# Buffer.net
KiCad netlist of a schematic drawn in Altium Designer
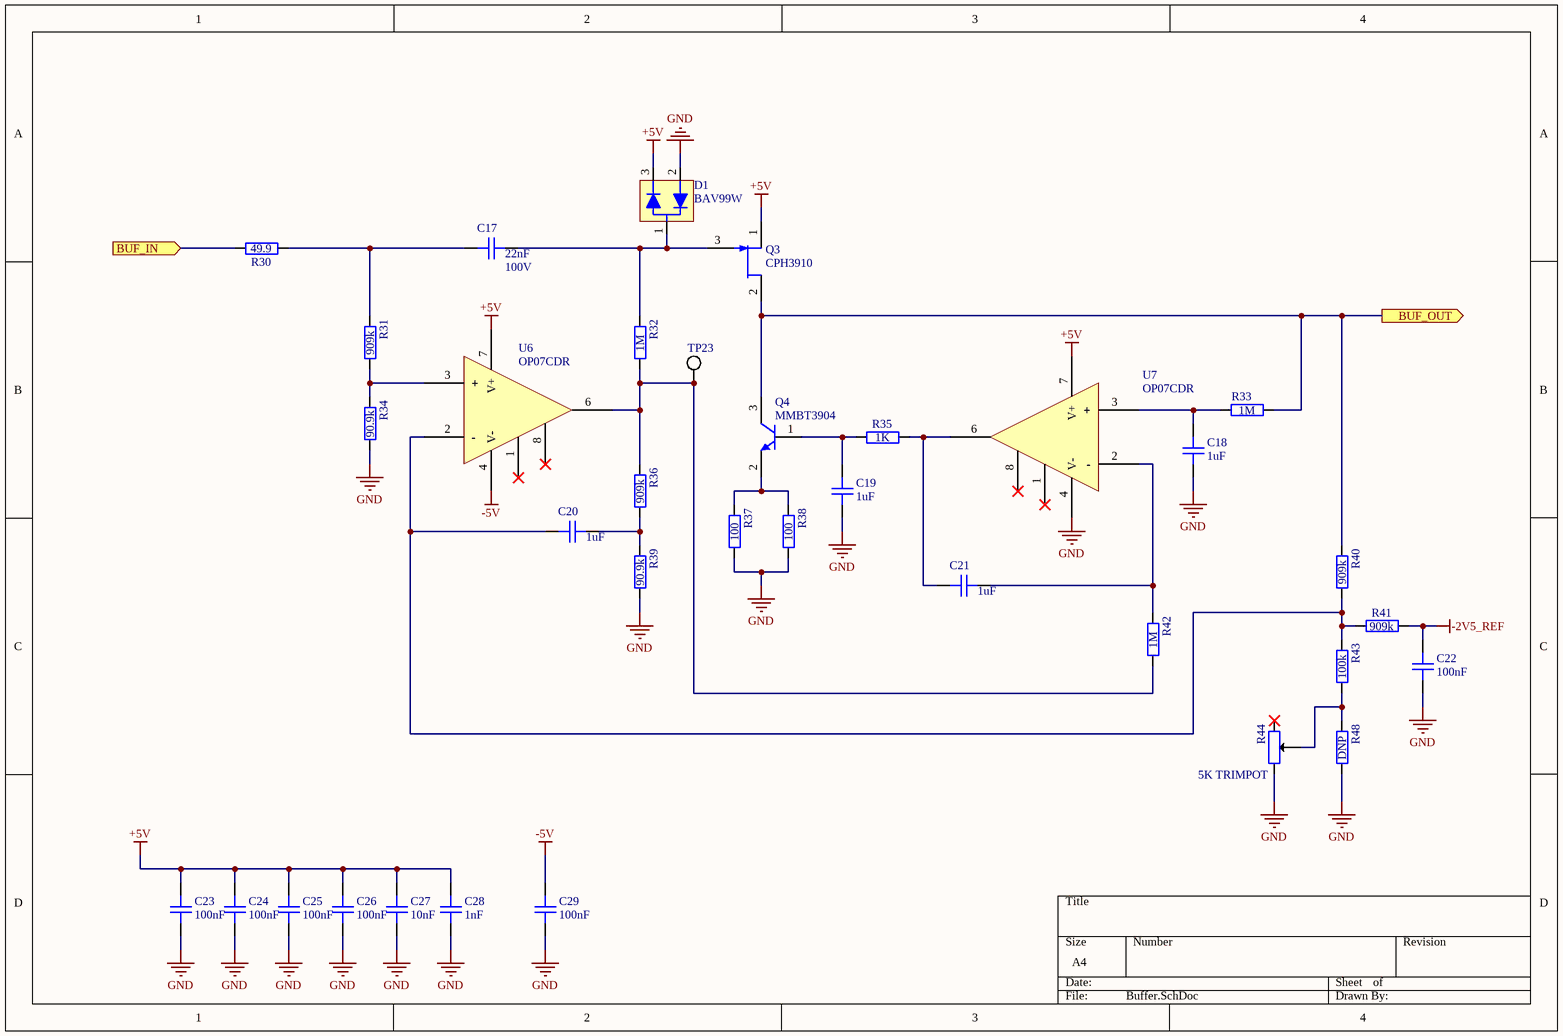
[diagram p0: Buffer.SchDoc]

(export (version "E")
  (design (tool "Eeschema 10.0.6"))
  (components
    (comp (ref "C17")
      (value "22nF")
      (footprint "GEN_C_0603")
      (fields (field (name "VOLTAGE RATING") "100V"))
      (libsource (lib "DSO") (part "CAP 22nF 100V X7R 0603"))
    )
    (comp (ref "C18")
      (value "1uF")
      (footprint "GEN_C_0402")
      (libsource (lib "DSO") (part "CAP 1uF 25V X5R 0402"))
    )
    (comp (ref "C19")
      (value "1uF")
      (footprint "GEN_C_0402")
      (libsource (lib "DSO") (part "CAP 1uF 25V X5R 0402"))
    )
    (comp (ref "C20")
      (value "1uF")
      (footprint "GEN_C_0402")
      (libsource (lib "DSO") (part "CAP 1uF 25V X5R 0402"))
    )
    (comp (ref "C21")
      (value "1uF")
      (footprint "GEN_C_0402")
      (libsource (lib "DSO") (part "CAP 1uF 25V X5R 0402"))
    )
    (comp (ref "C22")
      (value "100nF")
      (footprint "GEN_C_0402")
      (libsource (lib "DSO") (part "CAP 100nF 16V X7R 0402"))
    )
    (comp (ref "C23")
      (value "100nF")
      (footprint "GEN_C_0402")
      (libsource (lib "DSO") (part "CAP 100nF 16V X7R 0402"))
    )
    (comp (ref "C24")
      (value "100nF")
      (footprint "GEN_C_0402")
      (libsource (lib "DSO") (part "CAP 100nF 16V X7R 0402"))
    )
    (comp (ref "C25")
      (value "100nF")
      (footprint "GEN_C_0402")
      (libsource (lib "DSO") (part "CAP 100nF 16V X7R 0402"))
    )
    (comp (ref "C26")
      (value "100nF")
      (footprint "GEN_C_0402")
      (libsource (lib "DSO") (part "CAP 100nF 16V X7R 0402"))
    )
    (comp (ref "C27")
      (value "10nF")
      (footprint "GEN_C_0402")
      (libsource (lib "DSO") (part "CAP 10nF 50V X7R 0402"))
    )
    (comp (ref "C28")
      (value "1nF")
      (footprint "GEN_C_0402")
      (libsource (lib "DSO") (part "CAP 1nF 50V C0G 0402"))
    )
    (comp (ref "C29")
      (value "100nF")
      (footprint "GEN_C_0402")
      (libsource (lib "DSO") (part "CAP 100nF 16V X7R 0402"))
    )
    (comp (ref "D1")
      (value "BAV99W")
      (footprint "GEN_SOT_323")
      (libsource (lib "DSO") (part "DIODE ARRAY BAV99W"))
    )
    (comp (ref "Q3")
      (value "CPH3910")
      (footprint "ON_SOT23_CPH3")
      (libsource (lib "DSO") (part "NJFET CPH3910"))
    )
    (comp (ref "Q4") (value "MMBT3904") (footprint "MMC_SOT23") (libsource (lib "DSO") (part "NPN MMBT3904")))
    (comp (ref "R30")
      (value "49.9")
      (footprint "GEN_R_0402")
      (fields (field (name "TOLERANCE") "1%"))
      (libsource (lib "DSO") (part "RES 49.9 OHM 1% 1/10W 0402"))
    )
    (comp (ref "R31")
      (value "909k")
      (footprint "GEN_R_0402")
      (fields (field (name "TOLERANCE") "1%"))
      (libsource (lib "DSO") (part "RES 909K OHM 1% 1/16W 0402"))
    )
    (comp (ref "R32")
      (value "1M")
      (footprint "GEN_R_0402")
      (fields (field (name "TOLERANCE") "1%"))
      (libsource (lib "DSO") (part "RES 1M OHM 1% 1/10W 0402"))
    )
    (comp (ref "R33")
      (value "1M")
      (footprint "GEN_R_0402")
      (fields (field (name "TOLERANCE") "1%"))
      (libsource (lib "") (part "RES 1M OHM 1% 1/10W 0402_1"))
    )
    (comp (ref "R34")
      (value "90.9k")
      (footprint "GEN_R_0402")
      (fields (field (name "TOLERANCE") "1%"))
      (libsource (lib "DSO") (part "RES 90.9K OHM 1% 1/16W 0402"))
    )
    (comp (ref "R35")
      (value "1K")
      (footprint "GEN_R_0402")
      (fields (field (name "TOLERANCE") "1%"))
      (libsource (lib "DSO") (part "RES 1K OHM 1% 1/10W 0402"))
    )
    (comp (ref "R36")
      (value "909k")
      (footprint "GEN_R_0402")
      (fields (field (name "TOLERANCE") "1%"))
      (libsource (lib "DSO") (part "RES 909K OHM 1% 1/16W 0402"))
    )
    (comp (ref "R37")
      (value "100")
      (footprint "GEN_R_0402")
      (fields (field (name "TOLERANCE") "1%"))
      (libsource (lib "DSO") (part "RES 100 OHM 1% 1/10W 0402"))
    )
    (comp (ref "R38")
      (value "100")
      (footprint "GEN_R_0402")
      (fields (field (name "TOLERANCE") "1%"))
      (libsource (lib "DSO") (part "RES 100 OHM 1% 1/10W 0402"))
    )
    (comp (ref "R39")
      (value "90.9k")
      (footprint "GEN_R_0402")
      (fields (field (name "TOLERANCE") "1%"))
      (libsource (lib "DSO") (part "RES 90.9K OHM 1% 1/16W 0402"))
    )
    (comp (ref "R40")
      (value "909k")
      (footprint "GEN_R_0402")
      (fields (field (name "TOLERANCE") "1%"))
      (libsource (lib "DSO") (part "RES 909K OHM 1% 1/16W 0402"))
    )
    (comp (ref "R41")
      (value "909k")
      (footprint "GEN_R_0402")
      (fields (field (name "TOLERANCE") "1%"))
      (libsource (lib "") (part "RES 909K OHM 1% 1/16W 0402_1"))
    )
    (comp (ref "R42")
      (value "1M")
      (footprint "GEN_R_0402")
      (fields (field (name "TOLERANCE") "1%"))
      (libsource (lib "DSO") (part "RES 1M OHM 1% 1/10W 0402"))
    )
    (comp (ref "R43")
      (value "100k")
      (footprint "GEN_R_0402")
      (fields (field (name "TOLERANCE") "1%"))
      (libsource (lib "DSO") (part "RES 100K OHM 1% 1/10W 0402"))
    )
    (comp (ref "R44")
      (value "5K TRIMPOT")
      (footprint "BOU_3mm_POT")
      (fields (field (name "TOLERANCE") "1%"))
      (libsource (lib "DSO") (part "TRIMMER 5K OHM 0.1W J LEAD TOP"))
    )
    (comp (ref "R48")
      (value "DNP")
      (footprint "GEN_R_0402")
      (fields (field (name "TOLERANCE") "1%"))
      (libsource (lib "DSO") (part "RES DNP 0402"))
    )
    (comp (ref "TP23") (value "PCB") (footprint "GEN_TP_PCB") (libsource (lib "DSO") (part "TP PCB 1mm")))
    (comp (ref "U6")
      (value "OP07CDR")
      (footprint "TI_SOIC8_D0008A")
      (libsource (lib "DSO") (part "IC OPAMP OP07CDR"))
    )
    (comp (ref "U7")
      (value "OP07CDR")
      (footprint "TI_SOIC8_D0008A")
      (libsource (lib "DSO") (part "IC OPAMP OP07CDR"))
    )
  )
  (nets
    (net (code "1") (name "+5V") (class "Default")
      (node (ref "C23") (pin "1") (pinfunction "1_1") (pintype "passive"))
      (node (ref "C24") (pin "1") (pinfunction "1_1") (pintype "passive"))
      (node (ref "C25") (pin "1") (pinfunction "1_1") (pintype "passive"))
      (node (ref "C26") (pin "1") (pinfunction "1_1") (pintype "passive"))
      (node (ref "C27") (pin "2") (pinfunction "2_2") (pintype "passive"))
      (node (ref "C28") (pin "2") (pinfunction "2_2") (pintype "passive"))
      (node (ref "D1") (pin "3") (pinfunction "3_3") (pintype "passive"))
      (node (ref "Q3") (pin "1") (pinfunction "S_1") (pintype "passive"))
      (node (ref "U6") (pin "7") (pinfunction "V+_7") (pintype "passive"))
      (node (ref "U7") (pin "7") (pinfunction "V+_7") (pintype "passive"))
    )
    (net (code "2") (name "-2V5_REF") (class "Default")
      (node (ref "C22") (pin "1") (pinfunction "1_1") (pintype "passive"))
      (node (ref "R41") (pin "1") (pinfunction "1_1") (pintype "passive"))
    )
    (net (code "3") (name "-5V") (class "Default")
      (node (ref "C29") (pin "1") (pinfunction "1_1") (pintype "passive"))
      (node (ref "U6") (pin "4") (pinfunction "V-_4") (pintype "passive"))
    )
    (net (code "4") (name "/BUF_IN") (class "Default")
      (node (ref "R30") (pin "1") (pinfunction "1_1") (pintype "passive"))
    )
    (net (code "5") (name "/BUF_OUT") (class "Default")
      (node (ref "Q3") (pin "2") (pinfunction "D_2") (pintype "passive"))
      (node (ref "Q4") (pin "3") (pinfunction "C_3") (pintype "passive"))
      (node (ref "R33") (pin "1") (pinfunction "1_1") (pintype "passive"))
      (node (ref "R40") (pin "2") (pinfunction "2_2") (pintype "passive"))
    )
    (net (code "6") (name "GND") (class "Default")
      (node (ref "C18") (pin "1") (pinfunction "1_1") (pintype "passive"))
      (node (ref "C19") (pin "1") (pinfunction "1_1") (pintype "passive"))
      (node (ref "C22") (pin "2") (pinfunction "2_2") (pintype "passive"))
      (node (ref "C23") (pin "2") (pinfunction "2_2") (pintype "passive"))
      (node (ref "C24") (pin "2") (pinfunction "2_2") (pintype "passive"))
      (node (ref "C25") (pin "2") (pinfunction "2_2") (pintype "passive"))
      (node (ref "C26") (pin "2") (pinfunction "2_2") (pintype "passive"))
      (node (ref "C27") (pin "1") (pinfunction "1_1") (pintype "passive"))
      (node (ref "C28") (pin "1") (pinfunction "1_1") (pintype "passive"))
      (node (ref "C29") (pin "2") (pinfunction "2_2") (pintype "passive"))
      (node (ref "D1") (pin "2") (pinfunction "2_2") (pintype "passive"))
      (node (ref "R34") (pin "1") (pinfunction "1_1") (pintype "passive"))
      (node (ref "R37") (pin "1") (pinfunction "1_1") (pintype "passive"))
      (node (ref "R38") (pin "1") (pinfunction "1_1") (pintype "passive"))
      (node (ref "R39") (pin "1") (pinfunction "1_1") (pintype "passive"))
      (node (ref "R44") (pin "3") (pinfunction "3_3") (pintype "passive"))
      (node (ref "R48") (pin "1") (pinfunction "1_1") (pintype "passive"))
      (node (ref "U7") (pin "4") (pinfunction "V-_4") (pintype "passive"))
    )
    (net (code "7") (name "Net-(C17-Pad2)") (class "Default")
      (node (ref "C17") (pin "2") (pinfunction "2_2") (pintype "passive"))
      (node (ref "R30") (pin "2") (pinfunction "2_2") (pintype "passive"))
      (node (ref "R31") (pin "2") (pinfunction "2_2") (pintype "passive"))
    )
    (net (code "8") (name "Net-(C20-Pad1)") (class "Default")
      (node (ref "C20") (pin "1") (pinfunction "1_1") (pintype "passive"))
      (node (ref "R36") (pin "1") (pinfunction "1_1") (pintype "passive"))
      (node (ref "R39") (pin "2") (pinfunction "2_2") (pintype "passive"))
    )
    (net (code "9") (name "Net-(Q3-G)") (class "Default")
      (node (ref "C17") (pin "1") (pinfunction "1_1") (pintype "passive"))
      (node (ref "D1") (pin "1") (pintype "passive"))
      (node (ref "Q3") (pin "3") (pinfunction "G_3") (pintype "passive"))
      (node (ref "R32") (pin "2") (pinfunction "2_2") (pintype "passive"))
    )
    (net (code "10") (name "Net-(Q4-B)") (class "Default")
      (node (ref "C19") (pin "2") (pinfunction "2_2") (pintype "passive"))
      (node (ref "Q4") (pin "1") (pinfunction "B_1") (pintype "passive"))
      (node (ref "R35") (pin "1") (pinfunction "1_1") (pintype "passive"))
    )
    (net (code "11") (name "Net-(Q4-E)") (class "Default")
      (node (ref "Q4") (pin "2") (pinfunction "E_2") (pintype "passive"))
      (node (ref "R37") (pin "2") (pinfunction "2_2") (pintype "passive"))
      (node (ref "R38") (pin "2") (pinfunction "2_2") (pintype "passive"))
    )
    (net (code "12") (name "Net-(R43-Pad1)") (class "Default")
      (node (ref "R43") (pin "1") (pinfunction "1_1") (pintype "passive"))
      (node (ref "R44") (pin "2") (pinfunction "2_2") (pintype "passive"))
      (node (ref "R48") (pin "2") (pinfunction "2_2") (pintype "passive"))
    )
    (net (code "13") (name "Net-(U6-+)") (class "Default")
      (node (ref "R31") (pin "1") (pinfunction "1_1") (pintype "passive"))
      (node (ref "R34") (pin "2") (pinfunction "2_2") (pintype "passive"))
      (node (ref "U6") (pin "3") (pinfunction "+_3") (pintype "passive"))
    )
    (net (code "14") (name "Net-(U6--)") (class "Default")
      (node (ref "C20") (pin "2") (pinfunction "2_2") (pintype "passive"))
      (node (ref "R40") (pin "1") (pinfunction "1_1") (pintype "passive"))
      (node (ref "R41") (pin "2") (pinfunction "2_2") (pintype "passive"))
      (node (ref "R43") (pin "2") (pinfunction "2_2") (pintype "passive"))
      (node (ref "U6") (pin "2") (pinfunction "-_2") (pintype "passive"))
    )
    (net (code "15") (name "Net-(U6-OUT)") (class "Default")
      (node (ref "R32") (pin "1") (pinfunction "1_1") (pintype "passive"))
      (node (ref "R36") (pin "2") (pinfunction "2_2") (pintype "passive"))
      (node (ref "R42") (pin "1") (pinfunction "1_1") (pintype "passive"))
      (node (ref "TP23") (pin "1") (pinfunction "1_1") (pintype "passive"))
      (node (ref "U6") (pin "6") (pinfunction "OUT_6") (pintype "passive"))
    )
    (net (code "16") (name "Net-(U7-+)") (class "Default")
      (node (ref "C18") (pin "2") (pinfunction "2_2") (pintype "passive"))
      (node (ref "R33") (pin "2") (pinfunction "2_2") (pintype "passive"))
      (node (ref "U7") (pin "3") (pinfunction "+_3") (pintype "passive"))
    )
    (net (code "17") (name "Net-(U7--)") (class "Default")
      (node (ref "C21") (pin "1") (pinfunction "1_1") (pintype "passive"))
      (node (ref "R42") (pin "2") (pinfunction "2_2") (pintype "passive"))
      (node (ref "U7") (pin "2") (pinfunction "-_2") (pintype "passive"))
    )
    (net (code "18") (name "Net-(U7-OUT)") (class "Default")
      (node (ref "C21") (pin "2") (pinfunction "2_2") (pintype "passive"))
      (node (ref "R35") (pin "2") (pinfunction "2_2") (pintype "passive"))
      (node (ref "U7") (pin "6") (pinfunction "OUT_6") (pintype "passive"))
    )
    (net (code "19") (name "unconnected-(R44-Pad1)") (class "Default")
      (node (ref "R44") (pin "1") (pinfunction "1_1") (pintype "passive+no_connect"))
    )
    (net (code "20") (name "unconnected-(U6-N1-Pad1)") (class "Default")
      (node (ref "U6") (pin "1") (pinfunction "N1_1") (pintype "passive+no_connect"))
    )
    (net (code "21") (name "unconnected-(U6-N2-Pad8)") (class "Default")
      (node (ref "U6") (pin "8") (pinfunction "N2_8") (pintype "passive+no_connect"))
    )
    (net (code "22") (name "unconnected-(U7-N1-Pad1)") (class "Default")
      (node (ref "U7") (pin "1") (pinfunction "N1_1") (pintype "passive+no_connect"))
    )
    (net (code "23") (name "unconnected-(U7-N2-Pad8)") (class "Default")
      (node (ref "U7") (pin "8") (pinfunction "N2_8") (pintype "passive+no_connect"))
    )
  )
)
